# Guitar_Input_Schematic.net
KiCad netlist of a schematic drawn in Altium Designer
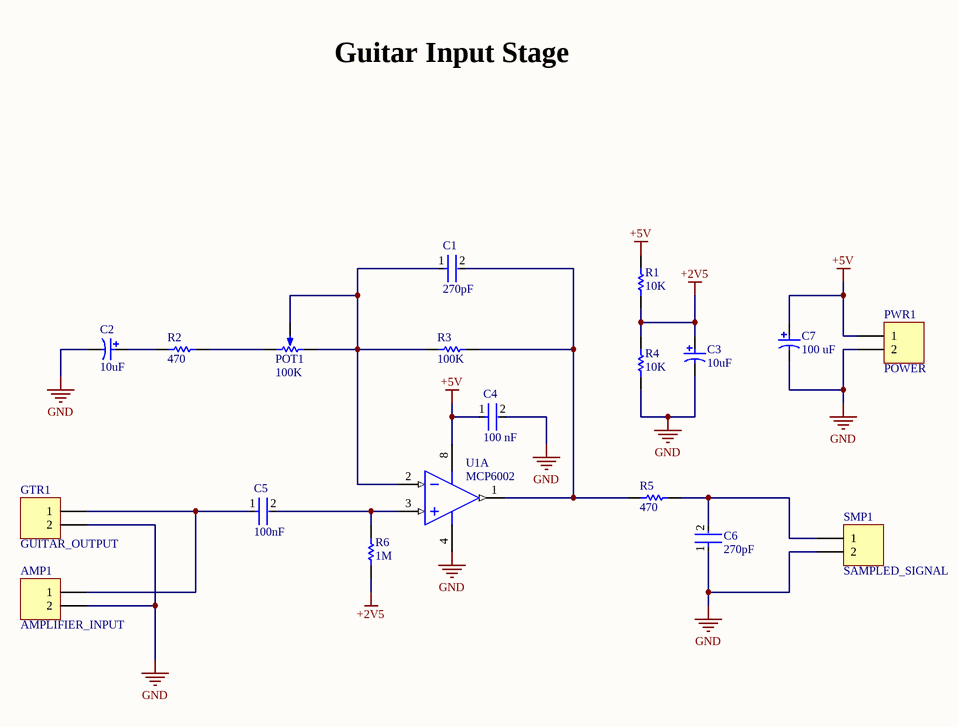
[diagram p0: Guitar Input Schematic.SchDoc]

(export (version "E")
  (design (tool "Eeschema 10.0.6"))
  (components
    (comp (ref "AMP1")
      (value "AMPLIFIER_INPUT")
      (footprint "HDR1X2")
      (description "Header, 2-Pin")
      (fields (field (name "PUBLISHER") "Altium Limited"))
      (libsource (lib "") (part "Header 2_1"))
    )
    (comp (ref "C1")
      (value "270pF")
      (footprint "FP-C0805C-DN-MFG")
      (description "C0805 270 pF C0G 30ppm/°C 5.00% 50 V")
      (fields (field (name "MANUFACTURER") "KEMET"))
      (libsource (lib "Altium Content Vault") (part "b4654b650e69147ec39a6b967a45e02"))
    )
    (comp (ref "C2")
      (value "10uF")
      (footprint "KEMT-A-3216-18-2_M")
      (description "Capacitor, Tantalum, 10 uF, +/- 10%, 10 V, -55 to 125 degC, 2-Pin SMD (1206), RoHS, Tape and Reel")
      (fields (field (name "TOLERANCE") "±10%") (field (name "MANUFACTURER") "Kemet"))
      (libsource (lib "Altium Content Vault") (part "CAP-P-2"))
    )
    (comp (ref "C3")
      (value "10uF")
      (footprint "KEMT-A-3216-18-2_M")
      (description "Capacitor, Tantalum, 10 uF, +/- 10%, 10 V, -55 to 125 degC, 2-Pin SMD (1206), RoHS, Tape and Reel")
      (fields (field (name "TOLERANCE") "±10%") (field (name "MANUFACTURER") "Kemet"))
      (libsource (lib "Altium Content Vault") (part "CAP-P-2"))
    )
    (comp (ref "C4")
      (value "100 nF")
      (footprint "FP-C0805C-DN-MFG")
      (description "CAP CER 0.1UF 50V X7R 0805")
      (fields
        (field (name "MANUFACTURER PART NUMBER") "C0805C104K5RACTU")
        (field (name "MANUFACTURER") "KEMET")
      )
      (libsource (lib "Altium Content Vault") (part "b4654b650e69147ec39a6b967a45e02"))
    )
    (comp (ref "C5")
      (value "100nF")
      (footprint "FP-C0805C-DN-MFG")
      (description "CAP CER 0.1UF 50V X7R 0805")
      (fields
        (field (name "MANUFACTURER PART NUMBER") "C0805C104K5RACTU")
        (field (name "MANUFACTURER") "KEMET")
      )
      (libsource (lib "Altium Content Vault") (part "b4654b650e69147ec39a6b967a45e02"))
    )
    (comp (ref "C6")
      (value "270pF")
      (footprint "FP-C0805C-DN-MFG")
      (description "C0805 270 pF C0G 30ppm/°C 5.00% 50 V")
      (fields (field (name "MANUFACTURER") "KEMET"))
      (libsource (lib "Altium Content Vault") (part "b4654b650e69147ec39a6b967a45e02"))
    )
    (comp (ref "C7")
      (value "100 uF")
      (footprint "KEMT-T491-D_L")
      (fields
        (field (name "MANUFACTURER") "Kemet")
        (field (name "VOLTAGE") "16V")
        (field (name "TOLERANCE") "10%")
      )
      (libsource (lib "Altium Content Vault") (part "CAP-P-2"))
    )
    (comp (ref "GTR1")
      (value "GUITAR_OUTPUT")
      (footprint "HDR1X2")
      (description "Header, 2-Pin")
      (fields (field (name "PUBLISHER") "Altium Limited"))
      (libsource (lib "") (part "Header 2_1"))
    )
    (comp (ref "POT1")
      (value "100K")
      (footprint "BOUR-3362P")
      (description "Square Trimpot(R) Trimming Potentiometer, 100 KOhm, 300 V, -55 to 125 degC, 3-Pin THD, RoHS, Tube")
      (fields (field (name "TOLERANCE") "1%"))
      (libsource (lib "Altium Content Vault") (part "RES-POT-3"))
    )
    (comp (ref "PWR1")
      (value "POWER")
      (footprint "HDR1X2")
      (description "Header, 2-Pin")
      (fields (field (name "PUBLISHER") "Altium Limited"))
      (libsource (lib "Miscellaneous Connectors") (part "Header 2"))
    )
    (comp (ref "R1")
      (value "10K")
      (footprint "RESC2013X60X35NL10T20")
      (description "Chip Resistor, 10 KOhm, +/- 1%, 0.125 W, -55 to 155 degC, 0805 (2012 Metric), RoHS, Tape and Reel")
      (fields (field (name "MANUFACTURER") "Yageo"))
      (libsource (lib "Altium Content Vault") (part "RES-2"))
    )
    (comp (ref "R2")
      (value "470")
      (footprint "RESC2013X70X40ML20T20")
      (description "Chip Resistor, 470 Ohm, +/- 1%, 0.125 W, -55 to 155 degC, 0805 (2012 Metric), RoHS, Tape and Reel")
      (fields (field (name "MANUFACTURER") "Panasonic"))
      (libsource (lib "Altium Content Vault") (part "RES-2"))
    )
    (comp (ref "R3")
      (value "100K")
      (footprint "RESC2013X60X35ML10T20")
      (description "Chip Resistor, 100 KOhm, +/- 1%, 0.125 W, -55 to 155 degC, 0805 (2012 Metric), RoHS, Tape and Reel")
      (fields (field (name "MANUFACTURER") "Yageo") (field (name "TOLERANCE") "1%"))
      (libsource (lib "Altium Content Vault") (part "RES-2"))
    )
    (comp (ref "R4")
      (value "10K")
      (footprint "RESC2013X60X35NL10T20")
      (description "Chip Resistor, 10 KOhm, +/- 1%, 0.125 W, -55 to 155 degC, 0805 (2012 Metric), RoHS, Tape and Reel")
      (fields (field (name "MANUFACTURER") "Yageo"))
      (libsource (lib "Altium Content Vault") (part "RES-2"))
    )
    (comp (ref "R5")
      (value "470")
      (footprint "RESC2013X70X40ML20T20")
      (description "Chip Resistor, 470 Ohm, +/- 1%, 0.125 W, -55 to 155 degC, 0805 (2012 Metric), RoHS, Tape and Reel")
      (fields (field (name "MANUFACTURER") "Panasonic"))
      (libsource (lib "Altium Content Vault") (part "RES-2"))
    )
    (comp (ref "R6")
      (value "1M")
      (footprint "RESC2013X70X40NL20T20")
      (fields (field (name "MANUFACTURER") "Panasonic"))
      (libsource (lib "Altium Content Vault") (part "RES-2"))
    )
    (comp (ref "SMP1")
      (value "SAMPLED_SIGNAL")
      (footprint "HDR1X2")
      (description "Header, 2-Pin")
      (fields (field (name "PUBLISHER") "Altium Limited"))
      (libsource (lib "Miscellaneous Connectors") (part "Header 2"))
    )
    (comp (ref "U1")
      (value "MCP6002")
      (footprint "SOIC-SN8_M")
      (description "1 MHz, Low-Power Operational Amplifier, 8-Pin SOIC, Extended Temperature")
      (libsource (lib "Altium Content Vault") (part "AMP-OPA-MCP6002-IL8"))
    )
  )
  (nets
    (net (code "1") (name "+2V5") (class "Default")
      (node (ref "C3") (pin "1") (pinfunction "1_1") (pintype "passive"))
      (node (ref "R1") (pin "1") (pinfunction "1_1") (pintype "passive"))
      (node (ref "R4") (pin "2") (pinfunction "2_2") (pintype "passive"))
      (node (ref "R6") (pin "1") (pinfunction "1_1") (pintype "passive"))
    )
    (net (code "2") (name "+5V") (class "Default")
      (node (ref "C4") (pin "1") (pinfunction "1_1") (pintype "passive"))
      (node (ref "C7") (pin "1") (pinfunction "1_1") (pintype "passive"))
      (node (ref "PWR1") (pin "1") (pinfunction "1_1") (pintype "passive"))
      (node (ref "R1") (pin "2") (pinfunction "2_2") (pintype "passive"))
      (node (ref "U1") (pin "8") (pinfunction "VDD_8") (pintype "power_in"))
    )
    (net (code "3") (name "GND") (class "Default")
      (node (ref "AMP1") (pin "2") (pinfunction "2_2") (pintype "passive"))
      (node (ref "C2") (pin "2") (pinfunction "2_2") (pintype "passive"))
      (node (ref "C3") (pin "2") (pinfunction "2_2") (pintype "passive"))
      (node (ref "C4") (pin "2") (pinfunction "2_2") (pintype "passive"))
      (node (ref "C6") (pin "1") (pinfunction "1_1") (pintype "passive"))
      (node (ref "C7") (pin "2") (pinfunction "2_2") (pintype "passive"))
      (node (ref "GTR1") (pin "2") (pinfunction "2_2") (pintype "passive"))
      (node (ref "PWR1") (pin "2") (pinfunction "2_2") (pintype "passive"))
      (node (ref "R4") (pin "1") (pinfunction "1_1") (pintype "passive"))
      (node (ref "SMP1") (pin "2") (pinfunction "2_2") (pintype "passive"))
      (node (ref "U1") (pin "4") (pinfunction "VSS_4") (pintype "power_in"))
    )
    (net (code "4") (name "Net-(AMP1-Pad1)") (class "Default")
      (node (ref "AMP1") (pin "1") (pinfunction "1_1") (pintype "passive"))
      (node (ref "C5") (pin "1") (pinfunction "1_1") (pintype "passive"))
      (node (ref "GTR1") (pin "1") (pinfunction "1_1") (pintype "passive"))
    )
    (net (code "5") (name "Net-(C2-Pad1)") (class "Default")
      (node (ref "C2") (pin "1") (pinfunction "1_1") (pintype "passive"))
      (node (ref "R2") (pin "1") (pinfunction "1_1") (pintype "passive"))
    )
    (net (code "6") (name "Net-(C6-Pad2)") (class "Default")
      (node (ref "C6") (pin "2") (pinfunction "2_2") (pintype "passive"))
      (node (ref "R5") (pin "2") (pinfunction "2_2") (pintype "passive"))
      (node (ref "SMP1") (pin "1") (pinfunction "1_1") (pintype "passive"))
    )
    (net (code "7") (name "Net-(POT1-CCW)") (class "Default")
      (node (ref "C1") (pin "1") (pinfunction "1_1") (pintype "passive"))
      (node (ref "POT1") (pin "1") (pinfunction "CCW_1") (pintype "passive"))
      (node (ref "POT1") (pin "2") (pinfunction "S_2") (pintype "passive"))
      (node (ref "R3") (pin "1") (pinfunction "1_1") (pintype "passive"))
      (node (ref "U1") (pin "2") (pinfunction "VINA-_2") (pintype "input"))
    )
    (net (code "8") (name "Net-(POT1-CW)") (class "Default")
      (node (ref "POT1") (pin "3") (pinfunction "CW_3") (pintype "passive"))
      (node (ref "R2") (pin "2") (pinfunction "2_2") (pintype "passive"))
    )
    (net (code "9") (name "Net-(U1A-VINA+)") (class "Default")
      (node (ref "C5") (pin "2") (pinfunction "2_2") (pintype "passive"))
      (node (ref "R6") (pin "2") (pinfunction "2_2") (pintype "passive"))
      (node (ref "U1") (pin "3") (pinfunction "VINA+_3") (pintype "input"))
    )
    (net (code "10") (name "Net-(U1A-VOUTA)") (class "Default")
      (node (ref "C1") (pin "2") (pinfunction "2_2") (pintype "passive"))
      (node (ref "R3") (pin "2") (pinfunction "2_2") (pintype "passive"))
      (node (ref "R5") (pin "1") (pinfunction "1_1") (pintype "passive"))
      (node (ref "U1") (pin "1") (pinfunction "VOUTA_1") (pintype "output"))
    )
  )
)
